# Rocketometer2148_MPU9150_No_Oscillators_.net
KiCad netlist of a schematic drawn in EAGLE
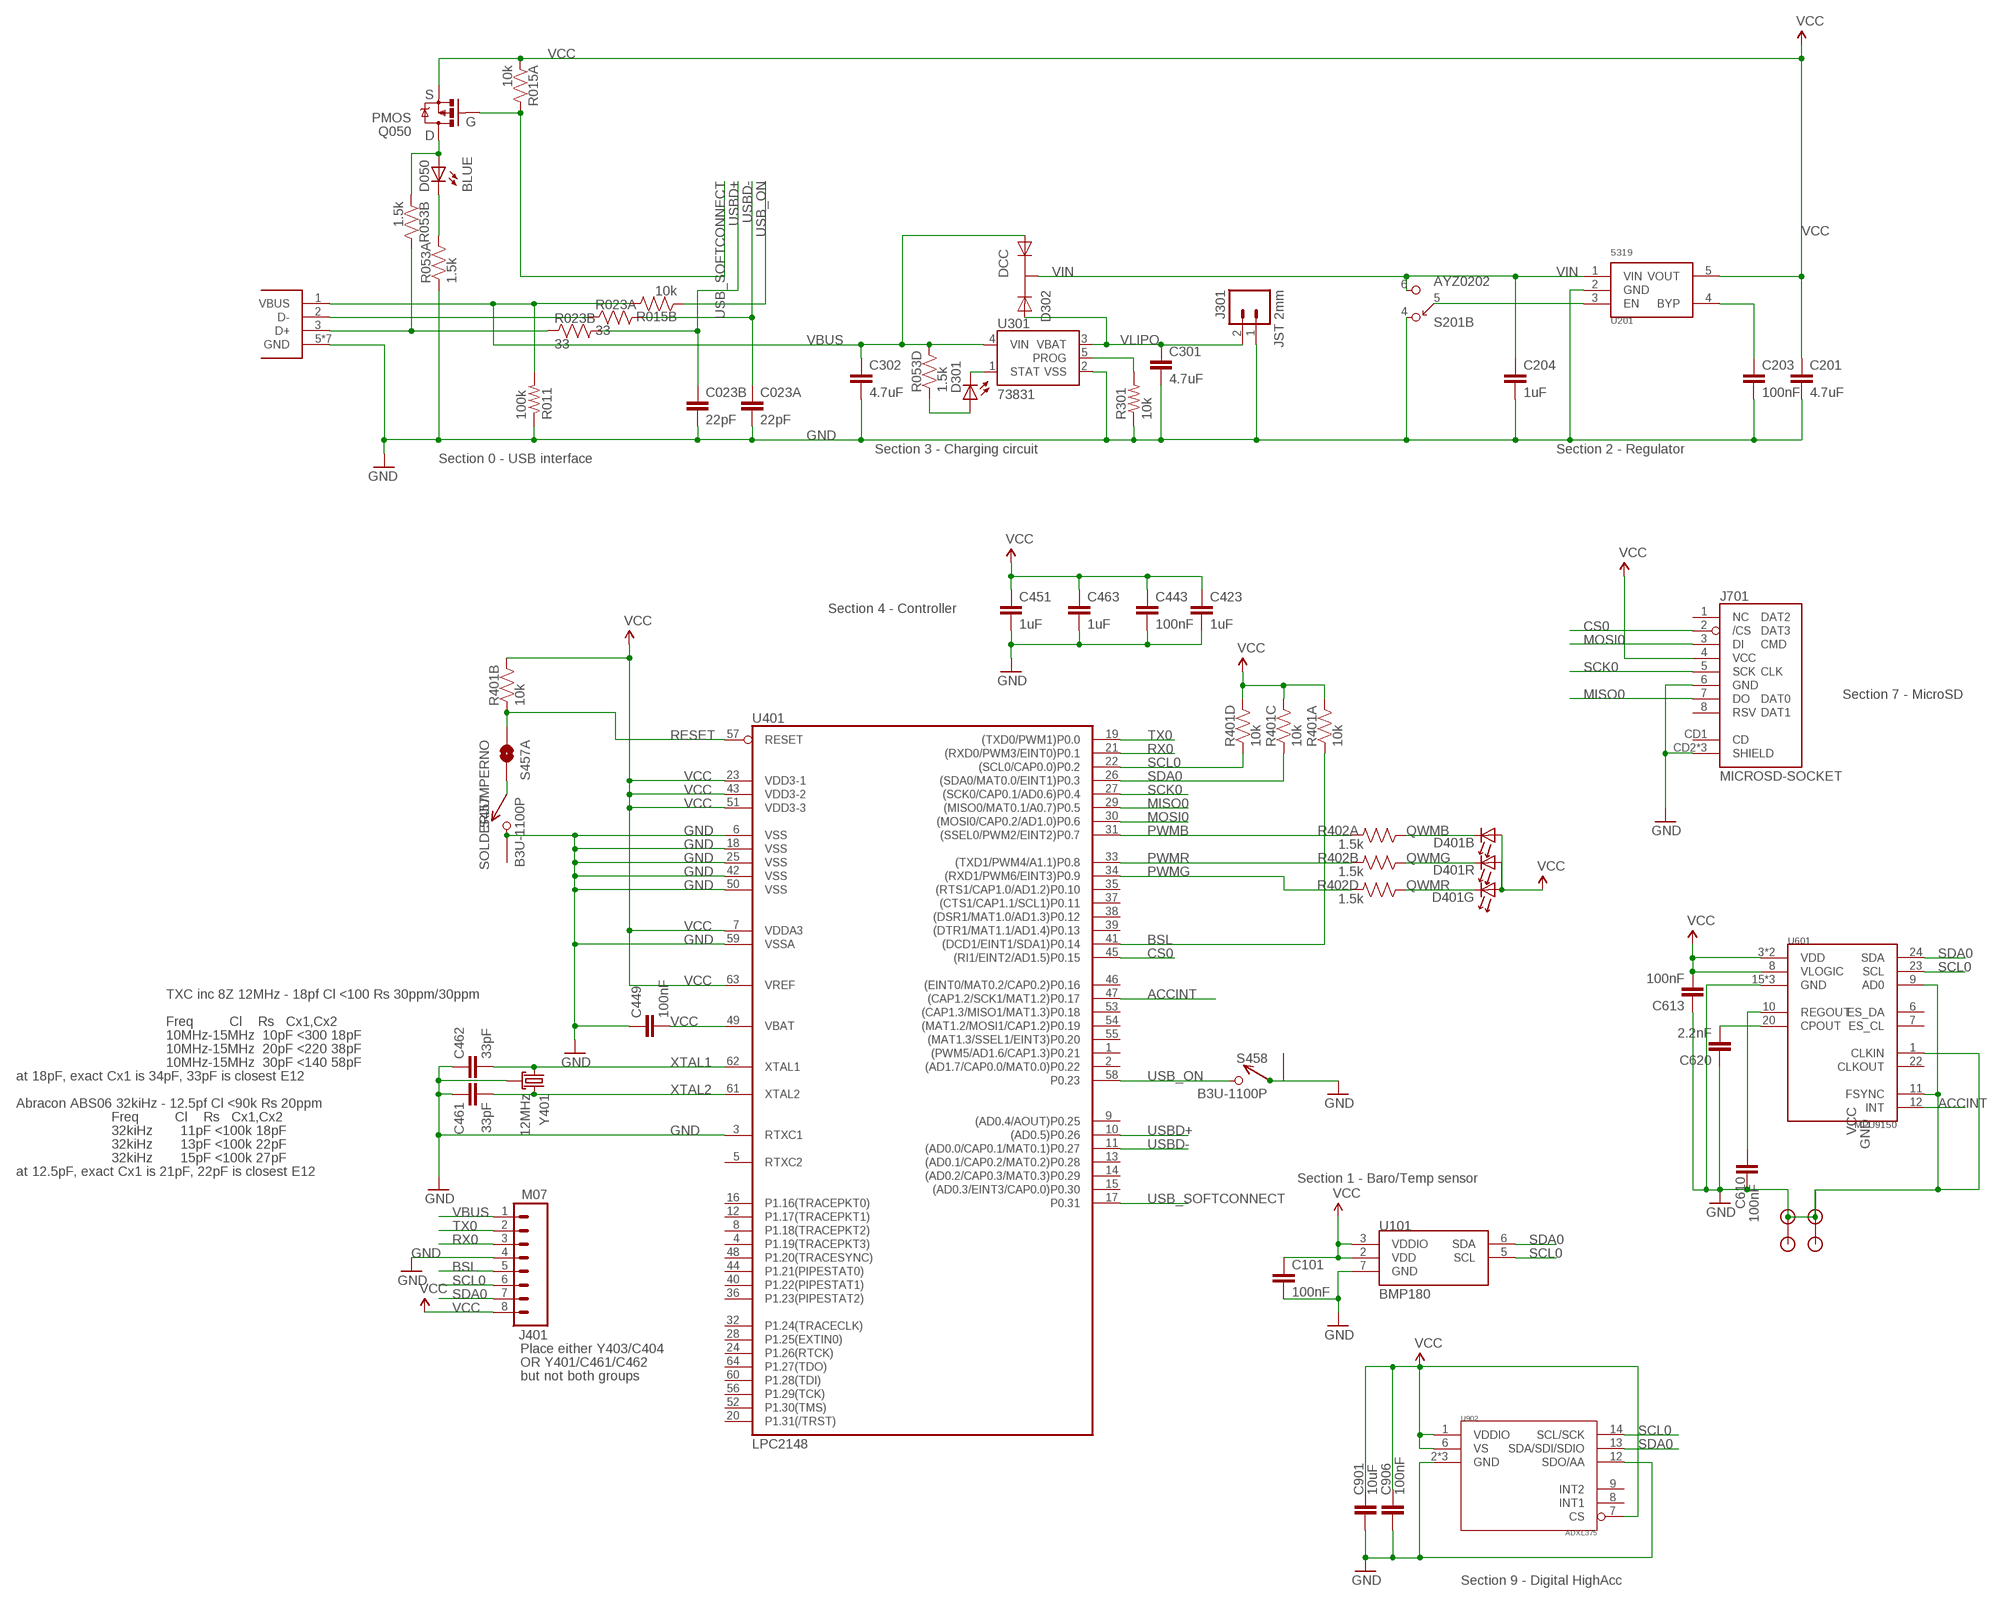
[diagram p0: schematic, sheet 1]

(export (version "E")
  (design (tool "Eeschema 10.0.6"))
  (components
    (comp (ref "C023")
      (value "22pF")
      (footprint "eagle-import:CKCM25")
      (fields (field (name "DIGIKEY") "445-1860-1-ND"))
      (libsource (lib "eagle-import") (part "CKCM25"))
    )
    (comp (ref "C101")
      (value "100nF")
      (footprint "eagle-import:0402-CAP")
      (libsource (lib "eagle-import") (part "CAP0402-CAP"))
    )
    (comp (ref "C201")
      (value "4.7uF")
      (footprint "eagle-import:0402-CAP")
      (libsource (lib "eagle-import") (part "CAP0402-CAP"))
    )
    (comp (ref "C203")
      (value "100nF")
      (footprint "eagle-import:0402-CAP")
      (libsource (lib "eagle-import") (part "CAP0402-CAP"))
    )
    (comp (ref "C204")
      (value "1uF")
      (footprint "eagle-import:0402-CAP")
      (libsource (lib "eagle-import") (part "CAP0402-CAP"))
    )
    (comp (ref "C301")
      (value "4.7uF")
      (footprint "eagle-import:0402-CAP")
      (libsource (lib "eagle-import") (part "CAP0402-CAP"))
    )
    (comp (ref "C302")
      (value "4.7uF")
      (footprint "eagle-import:0402-CAP")
      (libsource (lib "eagle-import") (part "CAP0402-CAP"))
    )
    (comp (ref "C423")
      (value "1uF")
      (footprint "eagle-import:0402-CAP")
      (libsource (lib "eagle-import") (part "CAP0402-CAP"))
    )
    (comp (ref "C443")
      (value "100nF")
      (footprint "eagle-import:0402-CAP")
      (libsource (lib "eagle-import") (part "CAP0402-CAP"))
    )
    (comp (ref "C449")
      (value "100nF")
      (footprint "eagle-import:0402-CAP")
      (libsource (lib "eagle-import") (part "CAP0402-CAP"))
    )
    (comp (ref "C451")
      (value "1uF")
      (footprint "eagle-import:0402-CAP")
      (libsource (lib "eagle-import") (part "CAP0402-CAP"))
    )
    (comp (ref "C461")
      (value "33pF")
      (footprint "eagle-import:0402-CAP")
      (libsource (lib "eagle-import") (part "CAP0402-CAP"))
    )
    (comp (ref "C462")
      (value "33pF")
      (footprint "eagle-import:0402-CAP")
      (libsource (lib "eagle-import") (part "CAP0402-CAP"))
    )
    (comp (ref "C463")
      (value "1uF")
      (footprint "eagle-import:0402-CAP")
      (libsource (lib "eagle-import") (part "CAP0402-CAP"))
    )
    (comp (ref "C610")
      (value "100nF")
      (footprint "eagle-import:0402-CAP")
      (libsource (lib "eagle-import") (part "CAP0402-CAP"))
    )
    (comp (ref "C613")
      (value "100nF")
      (footprint "eagle-import:0402-CAP")
      (libsource (lib "eagle-import") (part "CAP0402-CAP"))
    )
    (comp (ref "C620")
      (value "2.2nF")
      (footprint "eagle-import:0402-CAP")
      (libsource (lib "eagle-import") (part "CAP0402-CAP"))
    )
    (comp (ref "C901")
      (value "10uF")
      (footprint "eagle-import:0603-CAP")
      (libsource (lib "eagle-import") (part "CAP0603-CAP"))
    )
    (comp (ref "C906")
      (value "100nF")
      (footprint "eagle-import:0402-CAP")
      (libsource (lib "eagle-import") (part "SparkFun-Passives_CAP0402-CAP"))
    )
    (comp (ref "D050")
      (value "BLUE")
      (footprint "eagle-import:LED-0603")
      (libsource (lib "eagle-import") (part "LED0603"))
    )
    (comp (ref "D301")
      (value "YELLOW")
      (footprint "eagle-import:LED-0603")
      (libsource (lib "eagle-import") (part "LED0603"))
    )
    (comp (ref "D302")
      (value "DCC")
      (footprint "eagle-import:SOT-23-3")
      (libsource (lib "eagle-import") (part "PMEG2005CT"))
    )
    (comp (ref "D401")
      (value "SMLP36RGB2W(R)")
      (footprint "eagle-import:SMLP36")
      (fields (field (name "DIGIKEY") "846-1097-1-ND"))
      (libsource (lib "eagle-import") (part "SMLP36RGB2W(R)"))
    )
    (comp (ref "J001")
      (value "USB_MICROB_JSTGCT")
      (footprint "eagle-import:USB_MICROB_3075")
      (libsource (lib "eagle-import") (part "USB_MICROB_JSTGCT"))
    )
    (comp (ref "J301")
      (value "JST 2mm")
      (footprint "eagle-import:JST-2-SMD")
      (libsource (lib "eagle-import") (part "M02-JST-2MM-SMT"))
    )
    (comp (ref "J401")
      (value "M07")
      (footprint "eagle-import:1X08")
      (libsource (lib "eagle-import") (part "M081X08"))
    )
    (comp (ref "J701")
      (value "MICROSD-SOCKET")
      (footprint "eagle-import:MICROSD-SOCKET-PP")
      (libsource (lib "eagle-import") (part "MICROSD-SOCKET"))
    )
    (comp (ref "JP1")
      (value "STANDOFF")
      (footprint "eagle-import:STANDOFF")
      (libsource (lib "eagle-import") (part "STANDOFF"))
    )
    (comp (ref "JP2")
      (value "STANDOFF")
      (footprint "eagle-import:STANDOFF")
      (libsource (lib "eagle-import") (part "STANDOFF"))
    )
    (comp (ref "JP4")
      (value "STANDOFF")
      (footprint "eagle-import:STANDOFF")
      (libsource (lib "eagle-import") (part "STANDOFF"))
    )
    (comp (ref "JP5")
      (value "STANDOFF")
      (footprint "eagle-import:STANDOFF")
      (libsource (lib "eagle-import") (part "STANDOFF"))
    )
    (comp (ref "Q050")
      (value "PMOS")
      (footprint "eagle-import:SOT23-3")
      (libsource (lib "eagle-import") (part "MOSFET-PCHANNELSMD"))
    )
    (comp (ref "R011")
      (value "100k")
      (footprint "eagle-import:0402-RES")
      (libsource (lib "eagle-import") (part "RESISTOR0402-RES"))
    )
    (comp (ref "R015")
      (value "10k")
      (footprint "eagle-import:CRA02")
      (fields (field (name "DIGIKEY") "Y5103CT-ND"))
      (libsource (lib "eagle-import") (part "RP2EXB24V"))
    )
    (comp (ref "R023")
      (value "33")
      (footprint "eagle-import:CRA02")
      (libsource (lib "eagle-import") (part "RP2EXB24V"))
    )
    (comp (ref "R053")
      (value "1.5k")
      (footprint "eagle-import:CRA04")
      (fields (field (name "DIGIKEY") "CRA4S81.5KCT-ND"))
      (libsource (lib "eagle-import") (part "RP404"))
    )
    (comp (ref "R301")
      (value "10k")
      (footprint "eagle-import:0402-RES")
      (libsource (lib "eagle-import") (part "RESISTOR0402-RES"))
    )
    (comp (ref "R401")
      (value "10k")
      (footprint "eagle-import:CRA04")
      (fields (field (name "DIGIKEY") "CRA4S810KCT-ND"))
      (libsource (lib "eagle-import") (part "RP404"))
    )
    (comp (ref "R402")
      (value "1.5k")
      (footprint "eagle-import:CRA04")
      (fields (field (name "DIGIKEY") "CRA4S81.5KCT-ND"))
      (libsource (lib "eagle-import") (part "RP404"))
    )
    (comp (ref "S201")
      (value "AYZ0202")
      (footprint "eagle-import:AYZ0202")
      (libsource (lib "eagle-import") (part "AYZ0202"))
    )
    (comp (ref "S457")
      (value "B3U-1100P")
      (footprint "eagle-import:B3U-1100P")
      (fields (field (name "DIGIKEY") "SW1021CT-ND"))
      (libsource (lib "eagle-import") (part "B3U-1100P"))
    )
    (comp (ref "S457A")
      (value "SOLDERJUMPERNO")
      (footprint "eagle-import:SJ_2S-NO")
      (libsource (lib "eagle-import") (part "SOLDERJUMPERNO"))
    )
    (comp (ref "S458")
      (value "B3U-1100P")
      (footprint "eagle-import:B3U-1100P")
      (fields (field (name "DIGIKEY") "SW1021CT-ND"))
      (libsource (lib "eagle-import") (part "B3U-1100P"))
    )
    (comp (ref "U101")
      (value "BMP180")
      (footprint "eagle-import:BMP180")
      (libsource (lib "eagle-import") (part "BMP180"))
    )
    (comp (ref "U201")
      (value "5319")
      (footprint "eagle-import:SOT-23-5")
      (libsource (lib "eagle-import") (part "MIC5319D5"))
    )
    (comp (ref "U301")
      (value "73831")
      (footprint "eagle-import:SOT23-5")
      (libsource (lib "eagle-import") (part "MCP73831"))
    )
    (comp (ref "U401")
      (value "LPC2148")
      (footprint "eagle-import:SQFP-S-10X10-64")
      (libsource (lib "eagle-import") (part "LPC213X"))
    )
    (comp (ref "U601")
      (value "MPU9150")
      (footprint "eagle-import:LLGA24")
      (libsource (lib "eagle-import") (part "MPU9150"))
    )
    (comp (ref "U902")
      (value "ADXL375")
      (footprint "eagle-import:ADXL375")
      (libsource (lib "eagle-import") (part "ADXL375"))
    )
    (comp (ref "Y401")
      (value "12MHz")
      (footprint "eagle-import:CRYSTAL_SMD_2MM_2_5MM")
      (libsource (lib "eagle-import") (part "CX2520"))
    )
  )
  (nets
    (net (code "1") (name "/ACCINT") (class "Default")
      (node (ref "U401") (pin "47") (pinfunction "(CAP1.2/SCK1/MAT1.2)P0.17_47") (pintype "bidirectional"))
      (node (ref "U601") (pin "12") (pinfunction "INT_12") (pintype "bidirectional"))
    )
    (net (code "2") (name "/BSL") (class "Default")
      (node (ref "J401") (pin "5") (pinfunction "5_5") (pintype "passive"))
      (node (ref "R401") (pin "1") (pinfunction "1_1") (pintype "passive"))
      (node (ref "U401") (pin "41") (pinfunction "(DCD1/EINT1/SDA1)P0.14_41") (pintype "bidirectional"))
    )
    (net (code "3") (name "/CS0") (class "Default")
      (node (ref "J701") (pin "2") (pinfunction "/CS_2") (pintype "bidirectional"))
      (node (ref "U401") (pin "45") (pinfunction "(RI1/EINT2/AD1.5)P0.15_45") (pintype "bidirectional"))
    )
    (net (code "4") (name "/MISO0") (class "Default")
      (node (ref "J701") (pin "7") (pinfunction "DO_7") (pintype "bidirectional"))
      (node (ref "U401") (pin "29") (pinfunction "(MISO0/MAT0.1/A0.7)P0.5_29") (pintype "bidirectional"))
    )
    (net (code "5") (name "/MOSI0") (class "Default")
      (node (ref "J701") (pin "3") (pinfunction "DI_3") (pintype "bidirectional"))
      (node (ref "U401") (pin "30") (pinfunction "(MOSI0/CAP0.2/AD1.0)P0.6_30") (pintype "bidirectional"))
    )
    (net (code "6") (name "/PWMB") (class "Default")
      (node (ref "R402") (pin "8") (pinfunction "2_8") (pintype "passive"))
      (node (ref "U401") (pin "31") (pinfunction "(SSEL0/PWM2/EINT2)P0.7_31") (pintype "bidirectional"))
    )
    (net (code "7") (name "/PWMG") (class "Default")
      (node (ref "R402") (pin "5") (pinfunction "2_5") (pintype "passive"))
      (node (ref "U401") (pin "34") (pinfunction "(RXD1/PWM6/EINT3)P0.9_34") (pintype "bidirectional"))
    )
    (net (code "8") (name "/PWMR") (class "Default")
      (node (ref "R402") (pin "7") (pinfunction "2_7") (pintype "passive"))
      (node (ref "U401") (pin "33") (pinfunction "(TXD1/PWM4/A1.1)P0.8_33") (pintype "bidirectional"))
    )
    (net (code "9") (name "/QWMB") (class "Default")
      (node (ref "D401") (pin "1") (pinfunction "C_1") (pintype "passive"))
      (node (ref "R402") (pin "1") (pinfunction "1_1") (pintype "passive"))
    )
    (net (code "10") (name "/QWMG") (class "Default")
      (node (ref "D401") (pin "5") (pinfunction "C_5") (pintype "passive"))
      (node (ref "R402") (pin "4") (pinfunction "1_4") (pintype "passive"))
    )
    (net (code "11") (name "/QWMR") (class "Default")
      (node (ref "D401") (pin "3") (pinfunction "C_3") (pintype "passive"))
      (node (ref "R402") (pin "2") (pinfunction "1_2") (pintype "passive"))
    )
    (net (code "12") (name "/RESET") (class "Default")
      (node (ref "R401") (pin "2") (pinfunction "1_2") (pintype "passive"))
      (node (ref "S457A") (pin "1") (pinfunction "1_1") (pintype "passive"))
      (node (ref "U401") (pin "57") (pinfunction "RESET_57") (pintype "input"))
    )
    (net (code "13") (name "/RX0") (class "Default")
      (node (ref "J401") (pin "3") (pinfunction "3_3") (pintype "passive"))
      (node (ref "U401") (pin "21") (pinfunction "(RXD0/PWM3/EINT0)P0.1_21") (pintype "bidirectional"))
    )
    (net (code "14") (name "/SCK0") (class "Default")
      (node (ref "J701") (pin "5") (pinfunction "SCK_5") (pintype "bidirectional"))
      (node (ref "U401") (pin "27") (pinfunction "(SCK0/CAP0.1/AD0.6)P0.4_27") (pintype "bidirectional"))
    )
    (net (code "15") (name "/SCL0") (class "Default")
      (node (ref "J401") (pin "6") (pinfunction "6_6") (pintype "passive"))
      (node (ref "R401") (pin "4") (pinfunction "1_4") (pintype "passive"))
      (node (ref "U101") (pin "5") (pinfunction "SCL_5") (pintype "input"))
      (node (ref "U401") (pin "22") (pinfunction "(SCL0/CAP0.0)P0.2_22") (pintype "bidirectional"))
      (node (ref "U601") (pin "23") (pinfunction "SCL_23") (pintype "bidirectional"))
      (node (ref "U902") (pin "14") (pinfunction "SCL/SCK_14") (pintype "input"))
    )
    (net (code "16") (name "/SDA0") (class "Default")
      (node (ref "J401") (pin "7") (pinfunction "7_7") (pintype "passive"))
      (node (ref "R401") (pin "3") (pinfunction "1_3") (pintype "passive"))
      (node (ref "U101") (pin "6") (pinfunction "SDA_6") (pintype "bidirectional"))
      (node (ref "U401") (pin "26") (pinfunction "(SDA0/MAT0.0/EINT1)P0.3_26") (pintype "bidirectional"))
      (node (ref "U601") (pin "24") (pinfunction "SDA_24") (pintype "bidirectional"))
      (node (ref "U902") (pin "13") (pinfunction "SDA/SDI/SDIO_13") (pintype "bidirectional"))
    )
    (net (code "17") (name "/TX0") (class "Default")
      (node (ref "J401") (pin "2") (pinfunction "2_2") (pintype "passive"))
      (node (ref "U401") (pin "19") (pinfunction "(TXD0/PWM1)P0.0_19") (pintype "bidirectional"))
    )
    (net (code "18") (name "/USBD+") (class "Default")
      (node (ref "C023") (pin "2") (pinfunction "1_2") (pintype "passive"))
      (node (ref "R023") (pin "3") (pinfunction "2_3") (pintype "passive"))
      (node (ref "U401") (pin "10") (pinfunction "(AD0.5)P0.26_10") (pintype "bidirectional"))
    )
    (net (code "19") (name "/USBD-") (class "Default")
      (node (ref "C023") (pin "1") (pinfunction "1_1") (pintype "passive"))
      (node (ref "R023") (pin "4") (pinfunction "2_4") (pintype "passive"))
      (node (ref "U401") (pin "11") (pinfunction "(AD0.0/CAP0.1/MAT0.1)P0.27_11") (pintype "bidirectional"))
    )
    (net (code "20") (name "/USB_ON") (class "Default")
      (node (ref "R015") (pin "2") (pinfunction "1_2") (pintype "passive"))
      (node (ref "S458") (pin "P$2") (pinfunction "2_P$2") (pintype "bidirectional"))
      (node (ref "U401") (pin "58") (pinfunction "P0.23_58") (pintype "bidirectional"))
    )
    (net (code "21") (name "/USB_SOFTCONNECT") (class "Default")
      (node (ref "Q050") (pin "1") (pinfunction "G_1") (pintype "passive"))
      (node (ref "R015") (pin "4") (pinfunction "2_4") (pintype "passive"))
      (node (ref "U401") (pin "17") (pinfunction "P0.31_17") (pintype "output"))
    )
    (net (code "22") (name "/VBUS") (class "Default")
      (node (ref "C302") (pin "1") (pinfunction "1_1") (pintype "passive"))
      (node (ref "D302") (pin "1") (pinfunction "A1_1") (pintype "passive"))
      (node (ref "J001") (pin "1") (pinfunction "VBUS_1") (pintype "bidirectional"))
      (node (ref "J401") (pin "1") (pinfunction "1_1") (pintype "passive"))
      (node (ref "R011") (pin "2") (pinfunction "2_2") (pintype "passive"))
      (node (ref "R015") (pin "3") (pinfunction "2_3") (pintype "passive"))
      (node (ref "R053") (pin "5") (pinfunction "2_5") (pintype "passive"))
      (node (ref "U301") (pin "4") (pinfunction "VIN_4") (pintype "power_in"))
    )
    (net (code "23") (name "/VIN") (class "Default")
      (node (ref "C204") (pin "1") (pinfunction "1_1") (pintype "passive"))
      (node (ref "D302") (pin "3") (pinfunction "K_3") (pintype "passive"))
      (node (ref "S201") (pin "6") (pinfunction "P$2_6") (pintype "bidirectional"))
      (node (ref "U201") (pin "1") (pinfunction "VIN_1") (pintype "bidirectional"))
    )
    (net (code "24") (name "/VLIPO") (class "Default")
      (node (ref "C301") (pin "1") (pinfunction "1_1") (pintype "passive"))
      (node (ref "D302") (pin "2") (pinfunction "A2_2") (pintype "passive"))
      (node (ref "J301") (pin "2") (pinfunction "2_2") (pintype "passive"))
      (node (ref "U301") (pin "3") (pinfunction "VBAT_3") (pintype "power_in"))
    )
    (net (code "25") (name "/XTAL1") (class "Default")
      (node (ref "C462") (pin "2") (pinfunction "2_2") (pintype "passive"))
      (node (ref "U401") (pin "62") (pinfunction "XTAL1_62") (pintype "input"))
      (node (ref "Y401") (pin "1") (pinfunction "1_1") (pintype "passive"))
    )
    (net (code "26") (name "/XTAL2") (class "Default")
      (node (ref "C461") (pin "2") (pinfunction "2_2") (pintype "passive"))
      (node (ref "U401") (pin "61") (pinfunction "XTAL2_61") (pintype "output"))
      (node (ref "Y401") (pin "3") (pinfunction "2_3") (pintype "passive"))
    )
    (net (code "27") (name "GND") (class "Default")
      (node (ref "C023") (pin "3") (pinfunction "2_3") (pintype "passive"))
      (node (ref "C023") (pin "4") (pinfunction "2_4") (pintype "passive"))
      (node (ref "C101") (pin "2") (pinfunction "2_2") (pintype "passive"))
      (node (ref "C201") (pin "2") (pinfunction "2_2") (pintype "passive"))
      (node (ref "C203") (pin "2") (pinfunction "2_2") (pintype "passive"))
      (node (ref "C204") (pin "2") (pinfunction "2_2") (pintype "passive"))
      (node (ref "C301") (pin "2") (pinfunction "2_2") (pintype "passive"))
      (node (ref "C302") (pin "2") (pinfunction "2_2") (pintype "passive"))
      (node (ref "C423") (pin "2") (pinfunction "2_2") (pintype "passive"))
      (node (ref "C443") (pin "2") (pinfunction "2_2") (pintype "passive"))
      (node (ref "C449") (pin "1") (pinfunction "1_1") (pintype "passive"))
      (node (ref "C451") (pin "2") (pinfunction "2_2") (pintype "passive"))
      (node (ref "C461") (pin "1") (pinfunction "1_1") (pintype "passive"))
      (node (ref "C462") (pin "1") (pinfunction "1_1") (pintype "passive"))
      (node (ref "C463") (pin "2") (pinfunction "2_2") (pintype "passive"))
      (node (ref "C610") (pin "2") (pinfunction "2_2") (pintype "passive"))
      (node (ref "C613") (pin "1") (pinfunction "1_1") (pintype "passive"))
      (node (ref "C620") (pin "1") (pinfunction "1_1") (pintype "passive"))
      (node (ref "C901") (pin "2") (pinfunction "2_2") (pintype "passive"))
      (node (ref "C906") (pin "2") (pinfunction "2_2") (pintype "passive"))
      (node (ref "J001") (pin "5") (pinfunction "GND_5") (pintype "bidirectional"))
      (node (ref "J001") (pin "P$1") (pinfunction "GND_P$1") (pintype "bidirectional"))
      (node (ref "J001") (pin "P$10") (pinfunction "GND_P$10") (pintype "bidirectional"))
      (node (ref "J001") (pin "P$2") (pinfunction "GND_P$2") (pintype "bidirectional"))
      (node (ref "J001") (pin "P$3") (pinfunction "GND_P$3") (pintype "bidirectional"))
      (node (ref "J001") (pin "P$4") (pinfunction "GND_P$4") (pintype "bidirectional"))
      (node (ref "J001") (pin "P$8") (pinfunction "GND_P$8") (pintype "bidirectional"))
      (node (ref "J301") (pin "1") (pinfunction "1_1") (pintype "passive"))
      (node (ref "J401") (pin "4") (pinfunction "4_4") (pintype "passive"))
      (node (ref "J701") (pin "6") (pinfunction "GND_6") (pintype "bidirectional"))
      (node (ref "J701") (pin "CD2") (pinfunction "SHIELD_CD2") (pintype "bidirectional"))
      (node (ref "J701") (pin "GND1") (pinfunction "SHIELD_GND1") (pintype "bidirectional"))
      (node (ref "J701") (pin "GND3") (pinfunction "SHIELD_GND3") (pintype "bidirectional"))
      (node (ref "JP1") (pin "P$1") (pinfunction "P$1_P$1") (pintype "bidirectional"))
      (node (ref "JP2") (pin "P$1") (pinfunction "P$1_P$1") (pintype "bidirectional"))
      (node (ref "JP4") (pin "P$1") (pinfunction "P$1_P$1") (pintype "bidirectional"))
      (node (ref "JP5") (pin "P$1") (pinfunction "P$1_P$1") (pintype "bidirectional"))
      (node (ref "R011") (pin "1") (pinfunction "1_1") (pintype "passive"))
      (node (ref "R053") (pin "1") (pinfunction "1_1") (pintype "passive"))
      (node (ref "R301") (pin "1") (pinfunction "1_1") (pintype "passive"))
      (node (ref "S201") (pin "4") (pinfunction "P$1_4") (pintype "bidirectional"))
      (node (ref "S457") (pin "P$2") (pinfunction "2_P$2") (pintype "bidirectional"))
      (node (ref "S457") (pin "P$3") (pinfunction "1_P$3") (pintype "bidirectional"))
      (node (ref "S458") (pin "P$1") (pinfunction "1_P$1") (pintype "bidirectional"))
      (node (ref "S458") (pin "P$3") (pinfunction "1_P$3") (pintype "bidirectional"))
      (node (ref "U101") (pin "7") (pinfunction "GND_7") (pintype "power_in"))
      (node (ref "U201") (pin "2") (pinfunction "GND_2") (pintype "bidirectional"))
      (node (ref "U301") (pin "2") (pinfunction "VSS_2") (pintype "power_in"))
      (node (ref "U401") (pin "18") (pinfunction "VSS_18") (pintype "power_in"))
      (node (ref "U401") (pin "25") (pinfunction "VSS_25") (pintype "power_in"))
      (node (ref "U401") (pin "3") (pinfunction "RTXC1_3") (pintype "input"))
      (node (ref "U401") (pin "42") (pinfunction "VSS_42") (pintype "power_in"))
      (node (ref "U401") (pin "50") (pinfunction "VSS_50") (pintype "power_in"))
      (node (ref "U401") (pin "59") (pinfunction "VSSA_59") (pintype "power_in"))
      (node (ref "U401") (pin "6") (pinfunction "VSS_6") (pintype "power_in"))
      (node (ref "U601") (pin "1") (pinfunction "CLKIN_1") (pintype "bidirectional"))
      (node (ref "U601") (pin "11") (pinfunction "FSYNC_11") (pintype "bidirectional"))
      (node (ref "U601") (pin "15") (pinfunction "GND_15") (pintype "bidirectional"))
      (node (ref "U601") (pin "17") (pinfunction "GND_17") (pintype "bidirectional"))
      (node (ref "U601") (pin "18") (pinfunction "GND_18") (pintype "bidirectional"))
      (node (ref "U601") (pin "9") (pinfunction "AD0_9") (pintype "bidirectional"))
      (node (ref "U902") (pin "12") (pinfunction "SDO/AA_12") (pintype "bidirectional"))
      (node (ref "U902") (pin "2") (pinfunction "GND_2") (pintype "power_in"))
      (node (ref "U902") (pin "4") (pinfunction "GND_4") (pintype "power_in"))
      (node (ref "U902") (pin "5") (pinfunction "GND_5") (pintype "power_in"))
      (node (ref "Y401") (pin "2") (pinfunction "GND_2") (pintype "passive"))
      (node (ref "Y401") (pin "4") (pinfunction "GND_4") (pintype "passive"))
    )
    (net (code "28") (name "Net-(J001-D+)") (class "Default")
      (node (ref "J001") (pin "3") (pinfunction "D+_3") (pintype "bidirectional"))
      (node (ref "R023") (pin "2") (pinfunction "1_2") (pintype "passive"))
      (node (ref "R053") (pin "7") (pinfunction "2_7") (pintype "passive"))
    )
    (net (code "29") (name "Net-(J001-D-)") (class "Default")
      (node (ref "J001") (pin "2") (pinfunction "D-_2") (pintype "bidirectional"))
      (node (ref "R023") (pin "1") (pinfunction "1_1") (pintype "passive"))
    )
    (net (code "30") (name "Net-(Q050-D)") (class "Default")
      (node (ref "D050") (pin "A") (pinfunction "A_A") (pintype "passive"))
      (node (ref "Q050") (pin "3") (pinfunction "D_3") (pintype "passive"))
      (node (ref "R053") (pin "2") (pinfunction "1_2") (pintype "passive"))
    )
    (net (code "31") (name "Net-(R053A-2)") (class "Default")
      (node (ref "D050") (pin "C") (pinfunction "C_C") (pintype "passive"))
      (node (ref "R053") (pin "8") (pinfunction "2_8") (pintype "passive"))
    )
    (net (code "32") (name "Net-(R053D-1)") (class "Default")
      (node (ref "D301") (pin "A") (pinfunction "A_A") (pintype "passive"))
      (node (ref "R053") (pin "4") (pinfunction "1_4") (pintype "passive"))
    )
    (net (code "33") (name "Net-(S201B-P$3)") (class "Default")
      (node (ref "S201") (pin "5") (pinfunction "P$3_5") (pintype "bidirectional"))
      (node (ref "U201") (pin "3") (pinfunction "EN_3") (pintype "bidirectional"))
    )
    (net (code "34") (name "Net-(S457B-1)") (class "Default")
      (node (ref "S457") (pin "P$1") (pinfunction "1_P$1") (pintype "bidirectional"))
      (node (ref "S457A") (pin "2") (pinfunction "2_2") (pintype "passive"))
    )
    (net (code "35") (name "Net-(U201-BYP)") (class "Default")
      (node (ref "C203") (pin "1") (pinfunction "1_1") (pintype "passive"))
      (node (ref "U201") (pin "4") (pinfunction "BYP_4") (pintype "bidirectional"))
    )
    (net (code "36") (name "Net-(U301-PROG)") (class "Default")
      (node (ref "R301") (pin "2") (pinfunction "2_2") (pintype "passive"))
      (node (ref "U301") (pin "5") (pinfunction "PROG_5") (pintype "input"))
    )
    (net (code "37") (name "Net-(U301-STAT)") (class "Default")
      (node (ref "D301") (pin "C") (pinfunction "C_C") (pintype "passive"))
      (node (ref "U301") (pin "1") (pinfunction "STAT_1") (pintype "output"))
    )
    (net (code "38") (name "Net-(U601-CPOUT)") (class "Default")
      (node (ref "C620") (pin "2") (pinfunction "2_2") (pintype "passive"))
      (node (ref "U601") (pin "20") (pinfunction "CPOUT_20") (pintype "bidirectional"))
    )
    (net (code "39") (name "Net-(U601-REGOUT)") (class "Default")
      (node (ref "C610") (pin "1") (pinfunction "1_1") (pintype "passive"))
      (node (ref "U601") (pin "10") (pinfunction "REGOUT_10") (pintype "bidirectional"))
    )
    (net (code "40") (name "VCC") (class "Default")
      (node (ref "C101") (pin "1") (pinfunction "1_1") (pintype "passive"))
      (node (ref "C201") (pin "1") (pinfunction "1_1") (pintype "passive"))
      (node (ref "C423") (pin "1") (pinfunction "1_1") (pintype "passive"))
      (node (ref "C443") (pin "1") (pinfunction "1_1") (pintype "passive"))
      (node (ref "C449") (pin "2") (pinfunction "2_2") (pintype "passive"))
      (node (ref "C451") (pin "1") (pinfunction "1_1") (pintype "passive"))
      (node (ref "C463") (pin "1") (pinfunction "1_1") (pintype "passive"))
      (node (ref "C613") (pin "2") (pinfunction "2_2") (pintype "passive"))
      (node (ref "C901") (pin "1") (pinfunction "1_1") (pintype "passive"))
      (node (ref "C906") (pin "1") (pinfunction "1_1") (pintype "passive"))
      (node (ref "D401") (pin "2") (pinfunction "A_2") (pintype "passive"))
      (node (ref "D401") (pin "4") (pinfunction "A_4") (pintype "passive"))
      (node (ref "D401") (pin "6") (pinfunction "A_6") (pintype "passive"))
      (node (ref "J401") (pin "8") (pinfunction "8_8") (pintype "passive"))
      (node (ref "J701") (pin "4") (pinfunction "VCC_4") (pintype "bidirectional"))
      (node (ref "Q050") (pin "2") (pinfunction "S_2") (pintype "passive"))
      (node (ref "R015") (pin "1") (pinfunction "1_1") (pintype "passive"))
      (node (ref "R401") (pin "5") (pinfunction "2_5") (pintype "passive"))
      (node (ref "R401") (pin "6") (pinfunction "2_6") (pintype "passive"))
      (node (ref "R401") (pin "7") (pinfunction "2_7") (pintype "passive"))
      (node (ref "R401") (pin "8") (pinfunction "2_8") (pintype "passive"))
      (node (ref "U101") (pin "2") (pinfunction "VDD_2") (pintype "power_in"))
      (node (ref "U101") (pin "3") (pinfunction "VDDIO_3") (pintype "power_in"))
      (node (ref "U201") (pin "5") (pinfunction "VOUT_5") (pintype "bidirectional"))
      (node (ref "U401") (pin "23") (pinfunction "VDD3-1_23") (pintype "power_in"))
      (node (ref "U401") (pin "43") (pinfunction "VDD3-2_43") (pintype "power_in"))
      (node (ref "U401") (pin "49") (pinfunction "VBAT_49") (pintype "power_in"))
      (node (ref "U401") (pin "51") (pinfunction "VDD3-3_51") (pintype "power_in"))
      (node (ref "U401") (pin "63") (pinfunction "VREF_63") (pintype "input"))
      (node (ref "U401") (pin "7") (pinfunction "VDDA3_7") (pintype "power_in"))
      (node (ref "U601") (pin "13") (pinfunction "VDD_13") (pintype "bidirectional"))
      (node (ref "U601") (pin "3") (pinfunction "VDD_3") (pintype "bidirectional"))
      (node (ref "U601") (pin "8") (pinfunction "VLOGIC_8") (pintype "bidirectional"))
      (node (ref "U902") (pin "1") (pinfunction "VDDIO_1") (pintype "power_in"))
      (node (ref "U902") (pin "6") (pinfunction "VS_6") (pintype "power_in"))
      (node (ref "U902") (pin "7") (pinfunction "CS_7") (pintype "input"))
    )
    (net (code "41") (name "unconnected-(J701-CD-PadCD1)") (class "Default")
      (node (ref "J701") (pin "CD1") (pinfunction "CD_CD1") (pintype "bidirectional"))
    )
    (net (code "42") (name "unconnected-(J701-NC-Pad1)") (class "Default")
      (node (ref "J701") (pin "1") (pinfunction "NC_1") (pintype "bidirectional"))
    )
    (net (code "43") (name "unconnected-(J701-RSV-Pad8)") (class "Default")
      (node (ref "J701") (pin "8") (pinfunction "RSV_8") (pintype "bidirectional"))
    )
    (net (code "44") (name "unconnected-(U401-(AD0.1{slash}CAP0.2{slash}MAT0.2)P0.28-Pad13)") (class "Default")
      (node (ref "U401") (pin "13") (pinfunction "(AD0.1/CAP0.2/MAT0.2)P0.28_13") (pintype "bidirectional"))
    )
    (net (code "45") (name "unconnected-(U401-(AD0.2{slash}CAP0.3{slash}MAT0.3)P0.29-Pad14)") (class "Default")
      (node (ref "U401") (pin "14") (pinfunction "(AD0.2/CAP0.3/MAT0.3)P0.29_14") (pintype "bidirectional"))
    )
    (net (code "46") (name "unconnected-(U401-(AD0.3{slash}EINT3{slash}CAP0.0)P0.30-Pad15)") (class "Default")
      (node (ref "U401") (pin "15") (pinfunction "(AD0.3/EINT3/CAP0.0)P0.30_15") (pintype "bidirectional"))
    )
    (net (code "47") (name "unconnected-(U401-(AD0.4{slash}AOUT)P0.25-Pad9)") (class "Default")
      (node (ref "U401") (pin "9") (pinfunction "(AD0.4/AOUT)P0.25_9") (pintype "bidirectional"))
    )
    (net (code "48") (name "unconnected-(U401-(AD1.7{slash}CAP0.0{slash}MAT0.0)P0.22-Pad2)") (class "Default")
      (node (ref "U401") (pin "2") (pinfunction "(AD1.7/CAP0.0/MAT0.0)P0.22_2") (pintype "bidirectional"))
    )
    (net (code "49") (name "unconnected-(U401-(CAP1.3{slash}MISO1{slash}MAT1.3)P0.18-Pad53)") (class "Default")
      (node (ref "U401") (pin "53") (pinfunction "(CAP1.3/MISO1/MAT1.3)P0.18_53") (pintype "bidirectional"))
    )
    (net (code "50") (name "unconnected-(U401-(CTS1{slash}CAP1.1{slash}SCL1)P0.11-Pad37)") (class "Default")
      (node (ref "U401") (pin "37") (pinfunction "(CTS1/CAP1.1/SCL1)P0.11_37") (pintype "bidirectional"))
    )
    (net (code "51") (name "unconnected-(U401-(DSR1{slash}MAT1.0{slash}AD1.3)P0.12-Pad38)") (class "Default")
      (node (ref "U401") (pin "38") (pinfunction "(DSR1/MAT1.0/AD1.3)P0.12_38") (pintype "bidirectional"))
    )
    (net (code "52") (name "unconnected-(U401-(DTR1{slash}MAT1.1{slash}AD1.4)P0.13-Pad39)") (class "Default")
      (node (ref "U401") (pin "39") (pinfunction "(DTR1/MAT1.1/AD1.4)P0.13_39") (pintype "bidirectional"))
    )
    (net (code "53") (name "unconnected-(U401-(EINT0{slash}MAT0.2{slash}CAP0.2)P0.16-Pad46)") (class "Default")
      (node (ref "U401") (pin "46") (pinfunction "(EINT0/MAT0.2/CAP0.2)P0.16_46") (pintype "bidirectional"))
    )
    (net (code "54") (name "unconnected-(U401-(MAT1.2{slash}MOSI1{slash}CAP1.2)P0.19-Pad54)") (class "Default")
      (node (ref "U401") (pin "54") (pinfunction "(MAT1.2/MOSI1/CAP1.2)P0.19_54") (pintype "bidirectional"))
    )
    (net (code "55") (name "unconnected-(U401-(MAT1.3{slash}SSEL1{slash}EINT3)P0.20-Pad55)") (class "Default")
      (node (ref "U401") (pin "55") (pinfunction "(MAT1.3/SSEL1/EINT3)P0.20_55") (pintype "bidirectional"))
    )
    (net (code "56") (name "unconnected-(U401-(PWM5{slash}AD1.6{slash}CAP1.3)P0.21-Pad1)") (class "Default")
      (node (ref "U401") (pin "1") (pinfunction "(PWM5/AD1.6/CAP1.3)P0.21_1") (pintype "bidirectional"))
    )
    (net (code "57") (name "unconnected-(U401-(RTS1{slash}CAP1.0{slash}AD1.2)P0.10-Pad35)") (class "Default")
      (node (ref "U401") (pin "35") (pinfunction "(RTS1/CAP1.0/AD1.2)P0.10_35") (pintype "bidirectional"))
    )
    (net (code "58") (name "unconnected-(U401-P1.16(TRACEPKT0)-Pad16)") (class "Default")
      (node (ref "U401") (pin "16") (pinfunction "P1.16(TRACEPKT0)_16") (pintype "bidirectional"))
    )
    (net (code "59") (name "unconnected-(U401-P1.17(TRACEPKT1)-Pad12)") (class "Default")
      (node (ref "U401") (pin "12") (pinfunction "P1.17(TRACEPKT1)_12") (pintype "bidirectional"))
    )
    (net (code "60") (name "unconnected-(U401-P1.18(TRACEPKT2)-Pad8)") (class "Default")
      (node (ref "U401") (pin "8") (pinfunction "P1.18(TRACEPKT2)_8") (pintype "bidirectional"))
    )
    (net (code "61") (name "unconnected-(U401-P1.19(TRACEPKT3)-Pad4)") (class "Default")
      (node (ref "U401") (pin "4") (pinfunction "P1.19(TRACEPKT3)_4") (pintype "bidirectional"))
    )
    (net (code "62") (name "unconnected-(U401-P1.20(TRACESYNC)-Pad48)") (class "Default")
      (node (ref "U401") (pin "48") (pinfunction "P1.20(TRACESYNC)_48") (pintype "bidirectional"))
    )
    (net (code "63") (name "unconnected-(U401-P1.21(PIPESTAT0)-Pad44)") (class "Default")
      (node (ref "U401") (pin "44") (pinfunction "P1.21(PIPESTAT0)_44") (pintype "bidirectional"))
    )
    (net (code "64") (name "unconnected-(U401-P1.22(PIPESTAT1)-Pad40)") (class "Default")
      (node (ref "U401") (pin "40") (pinfunction "P1.22(PIPESTAT1)_40") (pintype "bidirectional"))
    )
    (net (code "65") (name "unconnected-(U401-P1.23(PIPESTAT2)-Pad36)") (class "Default")
      (node (ref "U401") (pin "36") (pinfunction "P1.23(PIPESTAT2)_36") (pintype "bidirectional"))
    )
    (net (code "66") (name "unconnected-(U401-P1.24(TRACECLK)-Pad32)") (class "Default")
      (node (ref "U401") (pin "32") (pinfunction "P1.24(TRACECLK)_32") (pintype "bidirectional"))
    )
    (net (code "67") (name "unconnected-(U401-P1.25(EXTIN0)-Pad28)") (class "Default")
      (node (ref "U401") (pin "28") (pinfunction "P1.25(EXTIN0)_28") (pintype "bidirectional"))
    )
    (net (code "68") (name "unconnected-(U401-P1.26(RTCK)-Pad24)") (class "Default")
      (node (ref "U401") (pin "24") (pinfunction "P1.26(RTCK)_24") (pintype "bidirectional"))
    )
    (net (code "69") (name "unconnected-(U401-P1.27(TDO)-Pad64)") (class "Default")
      (node (ref "U401") (pin "64") (pinfunction "P1.27(TDO)_64") (pintype "bidirectional"))
    )
    (net (code "70") (name "unconnected-(U401-P1.28(TDI)-Pad60)") (class "Default")
      (node (ref "U401") (pin "60") (pinfunction "P1.28(TDI)_60") (pintype "bidirectional"))
    )
    (net (code "71") (name "unconnected-(U401-P1.29(TCK)-Pad56)") (class "Default")
      (node (ref "U401") (pin "56") (pinfunction "P1.29(TCK)_56") (pintype "bidirectional"))
    )
    (net (code "72") (name "unconnected-(U401-P1.30(TMS)-Pad52)") (class "Default")
      (node (ref "U401") (pin "52") (pinfunction "P1.30(TMS)_52") (pintype "bidirectional"))
    )
    (net (code "73") (name "unconnected-(U401-P1.31({slash}TRST)-Pad20)") (class "Default")
      (node (ref "U401") (pin "20") (pinfunction "P1.31(/TRST)_20") (pintype "bidirectional"))
    )
    (net (code "74") (name "unconnected-(U401-RTXC2-Pad5)") (class "Default")
      (node (ref "U401") (pin "5") (pinfunction "RTXC2_5") (pintype "output"))
    )
    (net (code "75") (name "unconnected-(U601-CLKOUT-Pad22)") (class "Default")
      (node (ref "U601") (pin "22") (pinfunction "CLKOUT_22") (pintype "bidirectional"))
    )
    (net (code "76") (name "unconnected-(U601-ES_CL-Pad7)") (class "Default")
      (node (ref "U601") (pin "7") (pinfunction "ES_CL_7") (pintype "bidirectional"))
    )
    (net (code "77") (name "unconnected-(U601-ES_DA-Pad6)") (class "Default")
      (node (ref "U601") (pin "6") (pinfunction "ES_DA_6") (pintype "bidirectional"))
    )
    (net (code "78") (name "unconnected-(U902-INT1-Pad8)") (class "Default")
      (node (ref "U902") (pin "8") (pinfunction "INT1_8") (pintype "output"))
    )
    (net (code "79") (name "unconnected-(U902-INT2-Pad9)") (class "Default")
      (node (ref "U902") (pin "9") (pinfunction "INT2_9") (pintype "output"))
    )
  )
)
